# SCH_pi-i2c-hat_2025-04-26.net
KiCad netlist of a schematic drawn in EasyEDA
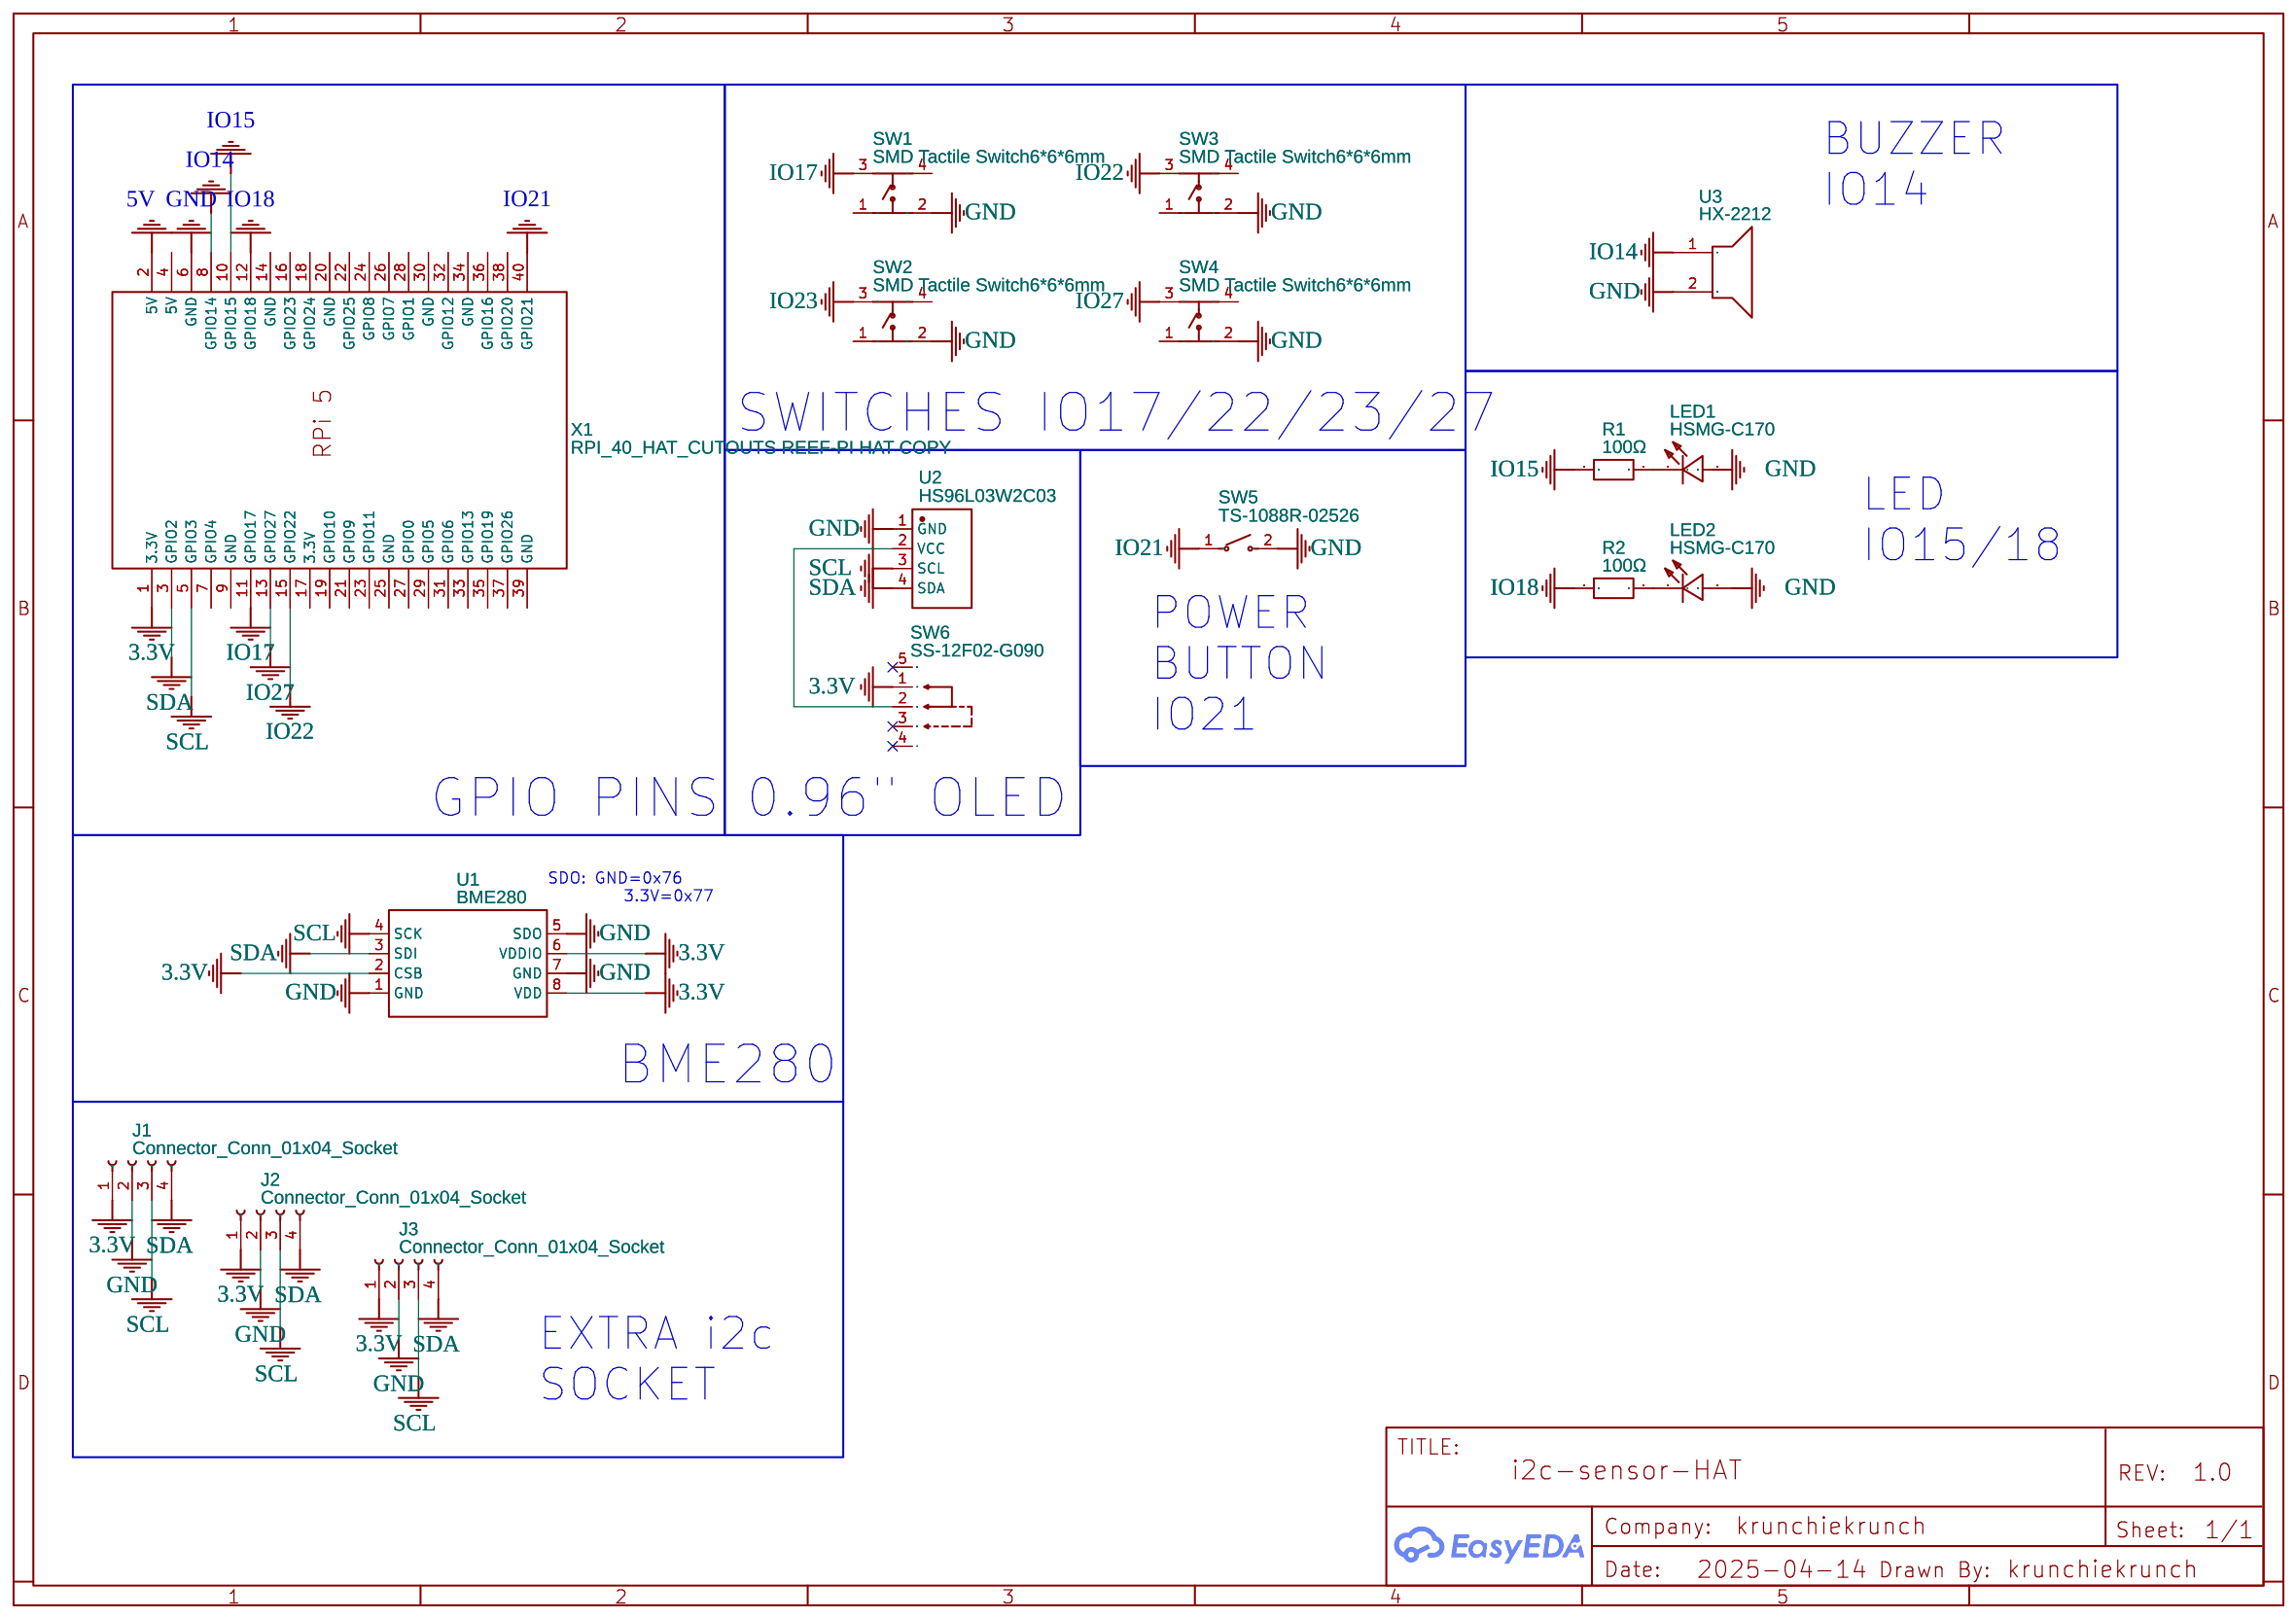
[diagram p0: schematic sheet]

(export (version "E")
  (design (tool "Eeschema 10.0.6"))
  (components
    (comp (ref "J1")
      (value "Connector_Conn_01x04_Socket")
      (libsource (lib "") (part "Connector_Conn_01x04_Socket"))
    )
    (comp (ref "J2")
      (value "Connector_Conn_01x04_Socket")
      (libsource (lib "") (part "Connector_Conn_01x04_Socket"))
    )
    (comp (ref "J3")
      (value "Connector_Conn_01x04_Socket")
      (libsource (lib "") (part "Connector_Conn_01x04_Socket"))
    )
    (comp (ref "LED1")
      (value "HSMG-C170")
      (fields (field (name "Manufacturer") "Broadcom/AVAGO(安华高)"))
      (libsource (lib "") (part "HSMG-C170"))
    )
    (comp (ref "LED2")
      (value "HSMG-C170")
      (fields (field (name "Manufacturer") "Broadcom/AVAGO(安华高)"))
      (libsource (lib "") (part "HSMG-C170"))
    )
    (comp (ref "R1")
      (value "100Ω")
      (fields
        (field (name "Manufacturer Part") "TRC0805D100RP0525Z")
        (field (name "Manufacturer") "EVER OHMS(天二科技)")
      )
      (libsource (lib "") (part "TRC0805D100RP0525Z"))
    )
    (comp (ref "R2")
      (value "100Ω")
      (fields
        (field (name "Manufacturer Part") "TRC0805D100RP0525Z")
        (field (name "Manufacturer") "EVER OHMS(天二科技)")
      )
      (libsource (lib "") (part "TRC0805D100RP0525Z"))
    )
    (comp (ref "SW1")
      (value "SMD Tactile Switch6*6*6mm")
      (fields (field (name "Manufacturer Part") "贴片轻触开关6*6*6mm"))
      (libsource (lib "") (part "SMD Tactile Switch6*6*6mm"))
    )
    (comp (ref "SW2")
      (value "SMD Tactile Switch6*6*6mm")
      (fields (field (name "Manufacturer Part") "贴片轻触开关6*6*6mm"))
      (libsource (lib "") (part "SMD Tactile Switch6*6*6mm"))
    )
    (comp (ref "SW3")
      (value "SMD Tactile Switch6*6*6mm")
      (fields (field (name "Manufacturer Part") "贴片轻触开关6*6*6mm"))
      (libsource (lib "") (part "SMD Tactile Switch6*6*6mm"))
    )
    (comp (ref "SW4")
      (value "SMD Tactile Switch6*6*6mm")
      (fields (field (name "Manufacturer Part") "贴片轻触开关6*6*6mm"))
      (libsource (lib "") (part "SMD Tactile Switch6*6*6mm"))
    )
    (comp (ref "SW5")
      (value "TS-1088R-02526")
      (fields (field (name "Manufacturer") "XUNPU(讯普)"))
      (libsource (lib "") (part "TS-1088R-02526"))
    )
    (comp (ref "SW6")
      (value "SS-12F02-G090")
      (fields (field (name "Manufacturer") "G-Switch(品赞)"))
      (libsource (lib "") (part "SS-12F02-G090"))
    )
    (comp (ref "U1")
      (value "BME280")
      (fields (field (name "Manufacturer") "Bosch(博世)"))
      (libsource (lib "") (part "BME280"))
    )
    (comp (ref "U2")
      (value "HS96L03W2C03")
      (fields (field (name "Manufacturer") "HS(汉昇)"))
      (libsource (lib "") (part "HS96L03W2C03"))
    )
    (comp (ref "U3") (value "HX-2212") (libsource (lib "") (part "HX-2212")))
    (comp (ref "X1")
      (value "RPI_40_HAT_CUTOUTS REEF-PI HAT COPY")
      (fields (field (name "Manufacturer") "Raspberry Pi 5 4GB"))
      (libsource (lib "") (part "Raspberry Pi 5"))
    )
  )
  (nets
    (net (code "1") (name "3.3V") (class "Default")
      (node (ref "J1") (pin "1") (pinfunction "Pin_1_1") (pintype "unspecified"))
      (node (ref "J2") (pin "1") (pinfunction "Pin_1_1") (pintype "unspecified"))
      (node (ref "J3") (pin "1") (pinfunction "Pin_1_1") (pintype "unspecified"))
      (node (ref "SW6") (pin "1") (pinfunction "1_1") (pintype "unspecified"))
      (node (ref "U1") (pin "2") (pinfunction "CSB_2") (pintype "unspecified"))
      (node (ref "U1") (pin "6") (pinfunction "VDDIO_6") (pintype "unspecified"))
      (node (ref "U1") (pin "8") (pinfunction "VDD_8") (pintype "unspecified"))
      (node (ref "X1") (pin "1") (pinfunction "3.3V_1") (pintype "passive"))
    )
    (net (code "2") (name "5V") (class "Default")
      (node (ref "X1") (pin "2") (pinfunction "5V_2") (pintype "passive"))
    )
    (net (code "3") (name "GND") (class "Default")
      (node (ref "J1") (pin "2") (pinfunction "Pin_2_2") (pintype "unspecified"))
      (node (ref "J2") (pin "2") (pinfunction "Pin_2_2") (pintype "unspecified"))
      (node (ref "J3") (pin "2") (pinfunction "Pin_2_2") (pintype "unspecified"))
      (node (ref "LED1") (pin "2") (pinfunction "2_2") (pintype "unspecified"))
      (node (ref "LED2") (pin "2") (pinfunction "2_2") (pintype "unspecified"))
      (node (ref "SW1") (pin "2") (pinfunction "2_2") (pintype "unspecified"))
      (node (ref "SW2") (pin "2") (pinfunction "2_2") (pintype "unspecified"))
      (node (ref "SW3") (pin "2") (pinfunction "2_2") (pintype "unspecified"))
      (node (ref "SW4") (pin "2") (pinfunction "2_2") (pintype "unspecified"))
      (node (ref "SW5") (pin "2") (pinfunction "2_2") (pintype "unspecified"))
      (node (ref "U1") (pin "1") (pinfunction "GND_1") (pintype "unspecified"))
      (node (ref "U1") (pin "5") (pinfunction "SDO_5") (pintype "unspecified"))
      (node (ref "U1") (pin "7") (pinfunction "GND_7") (pintype "unspecified"))
      (node (ref "U2") (pin "1") (pinfunction "GND_1") (pintype "unspecified"))
      (node (ref "U3") (pin "2") (pinfunction "2_2") (pintype "unspecified"))
      (node (ref "X1") (pin "6") (pinfunction "GND_6") (pintype "unspecified"))
    )
    (net (code "4") (name "IO14") (class "Default")
      (node (ref "U3") (pin "1") (pinfunction "1_1") (pintype "unspecified"))
      (node (ref "X1") (pin "8") (pinfunction "GPIO14_8") (pintype "bidirectional"))
    )
    (net (code "5") (name "IO15") (class "Default")
      (node (ref "R1") (pin "1") (pinfunction "1_1") (pintype "unspecified"))
      (node (ref "X1") (pin "10") (pinfunction "GPIO15_10") (pintype "bidirectional"))
    )
    (net (code "6") (name "IO17") (class "Default")
      (node (ref "SW1") (pin "3") (pinfunction "3_3") (pintype "unspecified"))
      (node (ref "X1") (pin "11") (pinfunction "GPIO17_11") (pintype "bidirectional"))
    )
    (net (code "7") (name "IO18") (class "Default")
      (node (ref "R2") (pin "1") (pinfunction "1_1") (pintype "unspecified"))
      (node (ref "X1") (pin "12") (pinfunction "GPIO18_12") (pintype "bidirectional"))
    )
    (net (code "8") (name "IO21") (class "Default")
      (node (ref "SW5") (pin "1") (pinfunction "1_1") (pintype "unspecified"))
      (node (ref "X1") (pin "40") (pinfunction "GPIO21_40") (pintype "bidirectional"))
    )
    (net (code "9") (name "IO22") (class "Default")
      (node (ref "SW3") (pin "3") (pinfunction "3_3") (pintype "unspecified"))
      (node (ref "X1") (pin "15") (pinfunction "GPIO22_15") (pintype "bidirectional"))
    )
    (net (code "10") (name "IO23") (class "Default")
      (node (ref "SW2") (pin "3") (pinfunction "3_3") (pintype "unspecified"))
    )
    (net (code "11") (name "IO27") (class "Default")
      (node (ref "SW4") (pin "3") (pinfunction "3_3") (pintype "unspecified"))
      (node (ref "X1") (pin "13") (pinfunction "GPIO27_13") (pintype "bidirectional"))
    )
    (net (code "12") (name "Net-(LED1-Pad1)") (class "Default")
      (node (ref "LED1") (pin "1") (pinfunction "1_1") (pintype "unspecified"))
      (node (ref "R1") (pin "2") (pinfunction "2_2") (pintype "unspecified"))
    )
    (net (code "13") (name "Net-(LED2-Pad1)") (class "Default")
      (node (ref "LED2") (pin "1") (pinfunction "1_1") (pintype "unspecified"))
      (node (ref "R2") (pin "2") (pinfunction "2_2") (pintype "unspecified"))
    )
    (net (code "14") (name "Net-(U2-VCC)") (class "Default")
      (node (ref "SW6") (pin "2") (pinfunction "2_2") (pintype "unspecified"))
      (node (ref "U2") (pin "2") (pinfunction "VCC_2") (pintype "unspecified"))
    )
    (net (code "15") (name "SCL") (class "Default")
      (node (ref "J1") (pin "3") (pinfunction "Pin_3_3") (pintype "unspecified"))
      (node (ref "J2") (pin "3") (pinfunction "Pin_3_3") (pintype "unspecified"))
      (node (ref "J3") (pin "3") (pinfunction "Pin_3_3") (pintype "unspecified"))
      (node (ref "U1") (pin "4") (pinfunction "SCK_4") (pintype "unspecified"))
      (node (ref "U2") (pin "3") (pinfunction "SCL_3") (pintype "unspecified"))
      (node (ref "X1") (pin "5") (pinfunction "GPIO3_5") (pintype "bidirectional"))
    )
    (net (code "16") (name "SDA") (class "Default")
      (node (ref "J1") (pin "4") (pinfunction "Pin_4_4") (pintype "unspecified"))
      (node (ref "J2") (pin "4") (pinfunction "Pin_4_4") (pintype "unspecified"))
      (node (ref "J3") (pin "4") (pinfunction "Pin_4_4") (pintype "unspecified"))
      (node (ref "U1") (pin "3") (pinfunction "SDI_3") (pintype "unspecified"))
      (node (ref "U2") (pin "4") (pinfunction "SDA_4") (pintype "unspecified"))
      (node (ref "X1") (pin "3") (pinfunction "GPIO2_3") (pintype "bidirectional"))
    )
    (net (code "17") (name "unconnected-(SW1-Pad1)") (class "Default")
      (node (ref "SW1") (pin "1") (pinfunction "1_1") (pintype "unspecified"))
    )
    (net (code "18") (name "unconnected-(SW1-Pad4)") (class "Default")
      (node (ref "SW1") (pin "4") (pinfunction "4_4") (pintype "unspecified"))
    )
    (net (code "19") (name "unconnected-(SW2-Pad1)") (class "Default")
      (node (ref "SW2") (pin "1") (pinfunction "1_1") (pintype "unspecified"))
    )
    (net (code "20") (name "unconnected-(SW2-Pad4)") (class "Default")
      (node (ref "SW2") (pin "4") (pinfunction "4_4") (pintype "unspecified"))
    )
    (net (code "21") (name "unconnected-(SW3-Pad1)") (class "Default")
      (node (ref "SW3") (pin "1") (pinfunction "1_1") (pintype "unspecified"))
    )
    (net (code "22") (name "unconnected-(SW3-Pad4)") (class "Default")
      (node (ref "SW3") (pin "4") (pinfunction "4_4") (pintype "unspecified"))
    )
    (net (code "23") (name "unconnected-(SW4-Pad1)") (class "Default")
      (node (ref "SW4") (pin "1") (pinfunction "1_1") (pintype "unspecified"))
    )
    (net (code "24") (name "unconnected-(SW4-Pad4)") (class "Default")
      (node (ref "SW4") (pin "4") (pinfunction "4_4") (pintype "unspecified"))
    )
    (net (code "25") (name "unconnected-(SW6-Pad3)") (class "Default")
      (node (ref "SW6") (pin "3") (pinfunction "3_3") (pintype "unspecified+no_connect"))
    )
    (net (code "26") (name "unconnected-(SW6-Pad4)") (class "Default")
      (node (ref "SW6") (pin "4") (pinfunction "4_4") (pintype "unspecified+no_connect"))
    )
    (net (code "27") (name "unconnected-(SW6-Pad5)") (class "Default")
      (node (ref "SW6") (pin "5") (pinfunction "5_5") (pintype "unspecified+no_connect"))
    )
    (net (code "28") (name "unconnected-(X1-3.3V-Pad17)") (class "Default")
      (node (ref "X1") (pin "17") (pinfunction "3.3V_17") (pintype "passive"))
    )
    (net (code "29") (name "unconnected-(X1-5V-Pad4)") (class "Default")
      (node (ref "X1") (pin "4") (pinfunction "5V_4") (pintype "passive"))
    )
    (net (code "30") (name "unconnected-(X1-GND-Pad9)") (class "Default")
      (node (ref "X1") (pin "9") (pinfunction "GND_9") (pintype "unspecified"))
    )
    (net (code "31") (name "unconnected-(X1-GND-Pad14)") (class "Default")
      (node (ref "X1") (pin "14") (pinfunction "GND_14") (pintype "unspecified"))
    )
    (net (code "32") (name "unconnected-(X1-GND-Pad20)") (class "Default")
      (node (ref "X1") (pin "20") (pinfunction "GND_20") (pintype "unspecified"))
    )
    (net (code "33") (name "unconnected-(X1-GND-Pad25)") (class "Default")
      (node (ref "X1") (pin "25") (pinfunction "GND_25") (pintype "unspecified"))
    )
    (net (code "34") (name "unconnected-(X1-GND-Pad30)") (class "Default")
      (node (ref "X1") (pin "30") (pinfunction "GND_30") (pintype "unspecified"))
    )
    (net (code "35") (name "unconnected-(X1-GND-Pad34)") (class "Default")
      (node (ref "X1") (pin "34") (pinfunction "GND_34") (pintype "unspecified"))
    )
    (net (code "36") (name "unconnected-(X1-GND-Pad39)") (class "Default")
      (node (ref "X1") (pin "39") (pinfunction "GND_39") (pintype "unspecified"))
    )
    (net (code "37") (name "unconnected-(X1-GPIO0-Pad27)") (class "Default")
      (node (ref "X1") (pin "27") (pinfunction "GPIO0_27") (pintype "unspecified"))
    )
    (net (code "38") (name "unconnected-(X1-GPIO1-Pad28)") (class "Default")
      (node (ref "X1") (pin "28") (pinfunction "GPIO1_28") (pintype "unspecified"))
    )
    (net (code "39") (name "unconnected-(X1-GPIO4-Pad7)") (class "Default")
      (node (ref "X1") (pin "7") (pinfunction "GPIO4_7") (pintype "bidirectional"))
    )
    (net (code "40") (name "unconnected-(X1-GPIO5-Pad29)") (class "Default")
      (node (ref "X1") (pin "29") (pinfunction "GPIO5_29") (pintype "bidirectional"))
    )
    (net (code "41") (name "unconnected-(X1-GPIO6-Pad31)") (class "Default")
      (node (ref "X1") (pin "31") (pinfunction "GPIO6_31") (pintype "bidirectional"))
    )
    (net (code "42") (name "unconnected-(X1-GPIO7-Pad26)") (class "Default")
      (node (ref "X1") (pin "26") (pinfunction "GPIO7_26") (pintype "bidirectional"))
    )
    (net (code "43") (name "unconnected-(X1-GPIO8-Pad24)") (class "Default")
      (node (ref "X1") (pin "24") (pinfunction "GPIO8_24") (pintype "bidirectional"))
    )
    (net (code "44") (name "unconnected-(X1-GPIO9-Pad21)") (class "Default")
      (node (ref "X1") (pin "21") (pinfunction "GPIO9_21") (pintype "bidirectional"))
    )
    (net (code "45") (name "unconnected-(X1-GPIO10-Pad19)") (class "Default")
      (node (ref "X1") (pin "19") (pinfunction "GPIO10_19") (pintype "bidirectional"))
    )
    (net (code "46") (name "unconnected-(X1-GPIO11-Pad23)") (class "Default")
      (node (ref "X1") (pin "23") (pinfunction "GPIO11_23") (pintype "bidirectional"))
    )
    (net (code "47") (name "unconnected-(X1-GPIO12-Pad32)") (class "Default")
      (node (ref "X1") (pin "32") (pinfunction "GPIO12_32") (pintype "bidirectional"))
    )
    (net (code "48") (name "unconnected-(X1-GPIO13-Pad33)") (class "Default")
      (node (ref "X1") (pin "33") (pinfunction "GPIO13_33") (pintype "bidirectional"))
    )
    (net (code "49") (name "unconnected-(X1-GPIO16-Pad36)") (class "Default")
      (node (ref "X1") (pin "36") (pinfunction "GPIO16_36") (pintype "bidirectional"))
    )
    (net (code "50") (name "unconnected-(X1-GPIO19-Pad35)") (class "Default")
      (node (ref "X1") (pin "35") (pinfunction "GPIO19_35") (pintype "bidirectional"))
    )
    (net (code "51") (name "unconnected-(X1-GPIO20-Pad38)") (class "Default")
      (node (ref "X1") (pin "38") (pinfunction "GPIO20_38") (pintype "bidirectional"))
    )
    (net (code "52") (name "unconnected-(X1-GPIO23-Pad16)") (class "Default")
      (node (ref "X1") (pin "16") (pinfunction "GPIO23_16") (pintype "bidirectional"))
    )
    (net (code "53") (name "unconnected-(X1-GPIO24-Pad18)") (class "Default")
      (node (ref "X1") (pin "18") (pinfunction "GPIO24_18") (pintype "bidirectional"))
    )
    (net (code "54") (name "unconnected-(X1-GPIO25-Pad22)") (class "Default")
      (node (ref "X1") (pin "22") (pinfunction "GPIO25_22") (pintype "bidirectional"))
    )
    (net (code "55") (name "unconnected-(X1-GPIO26-Pad37)") (class "Default")
      (node (ref "X1") (pin "37") (pinfunction "GPIO26_37") (pintype "bidirectional"))
    )
  )
)
